# termostat.net
KiCad netlist of a schematic drawn in EAGLE
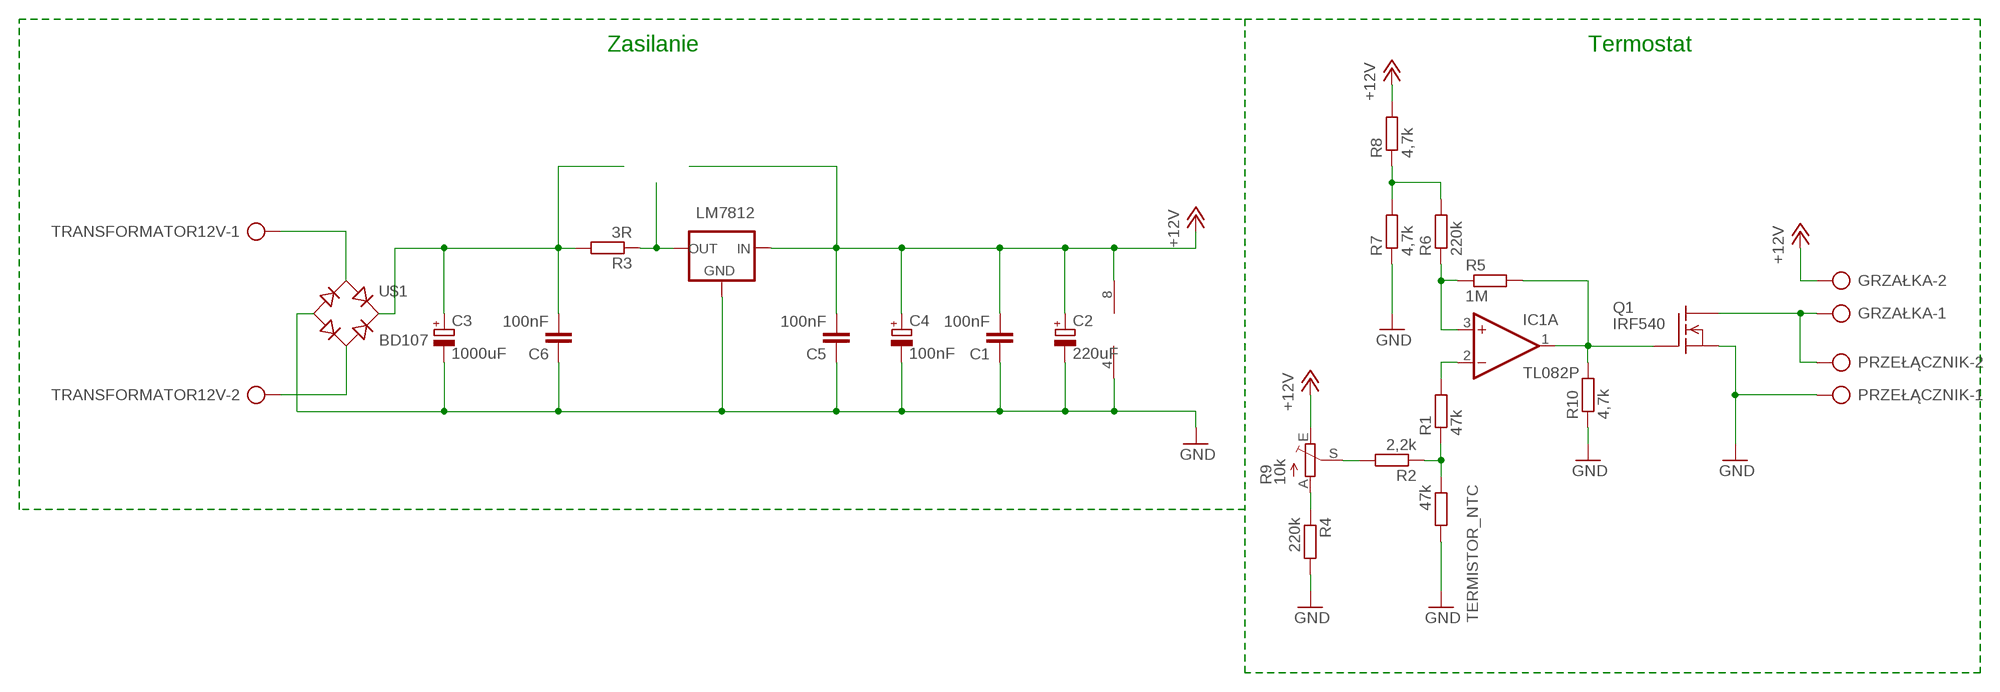
[diagram p0: schematic, sheet 1]

(export (version "E")
  (design (tool "Eeschema 10.0.6"))
  (components
    (comp (ref "C1")
      (value "100nF")
      (footprint "eagle-import:C50-45-75")
      (libsource (lib "eagle-import") (part "C-EU050-045-075"))
    )
    (comp (ref "C2")
      (value "220uF")
      (footprint "eagle-import:E2,5-6")
      (libsource (lib "eagle-import") (part "C-EU-POL'"))
    )
    (comp (ref "C3")
      (value "1000uF")
      (footprint "eagle-import:E5-13")
      (libsource (lib "eagle-import") (part "C-EU-POL"))
    )
    (comp (ref "C4")
      (value "100nF")
      (footprint "eagle-import:E2,5-6")
      (libsource (lib "eagle-import") (part "C-EU-POL'"))
    )
    (comp (ref "C5")
      (value "100nF")
      (footprint "eagle-import:C50-45-75")
      (libsource (lib "eagle-import") (part "C-EU050-045-075"))
    )
    (comp (ref "C6")
      (value "100nF")
      (footprint "eagle-import:C50-45-75")
      (libsource (lib "eagle-import") (part "C-EU050-045-075"))
    )
    (comp (ref "GRZAŁKA")
      (value "AK300/2")
      (footprint "eagle-import:AK300_2")
      (libsource (lib "eagle-import") (part "AK300/2"))
    )
    (comp (ref "IC1")
      (value "TL082P")
      (footprint "eagle-import:DIL08")
      (libsource (lib "eagle-import") (part "TL082P"))
    )
    (comp (ref "LM7812")
      (value "79XXS")
      (footprint "eagle-import:79XXS")
      (libsource (lib "eagle-import") (part "79XXS"))
    )
    (comp (ref "PRZEŁĄCZNIK")
      (value "AK300/2")
      (footprint "eagle-import:AK300_2")
      (libsource (lib "eagle-import") (part "AK300/2"))
    )
    (comp (ref "Q1")
      (value "IRF540")
      (footprint "eagle-import:TO220")
      (libsource (lib "eagle-import") (part "IRF540"))
    )
    (comp (ref "R1")
      (value "47k")
      (footprint "eagle-import:204_7")
      (libsource (lib "eagle-import") (part "R-EU7"))
    )
    (comp (ref "R2")
      (value "2,2k")
      (footprint "eagle-import:204_7")
      (libsource (lib "eagle-import") (part "R-EU7"))
    )
    (comp (ref "R3")
      (value "3R")
      (footprint "eagle-import:204_7")
      (libsource (lib "eagle-import") (part "R-EU7"))
    )
    (comp (ref "R4")
      (value "220k")
      (footprint "eagle-import:204_7")
      (libsource (lib "eagle-import") (part "R-EU7"))
    )
    (comp (ref "R5")
      (value "1M")
      (footprint "eagle-import:204_7")
      (libsource (lib "eagle-import") (part "R-EU7"))
    )
    (comp (ref "R6")
      (value "220k")
      (footprint "eagle-import:204_7")
      (libsource (lib "eagle-import") (part "R-EU7"))
    )
    (comp (ref "R7")
      (value "4,7k")
      (footprint "eagle-import:204_7")
      (libsource (lib "eagle-import") (part "R-EU7"))
    )
    (comp (ref "R8")
      (value "4,7k")
      (footprint "eagle-import:204_7")
      (libsource (lib "eagle-import") (part "R-EU7"))
    )
    (comp (ref "R9")
      (value "10k")
      (footprint "eagle-import:CA6V")
      (libsource (lib "eagle-import") (part "TRIM_EU-CA6V"))
    )
    (comp (ref "R10")
      (value "4,7k")
      (footprint "eagle-import:204_7")
      (libsource (lib "eagle-import") (part "R-EU7"))
    )
    (comp (ref "TERMISTOR_NTC")
      (value "47k")
      (footprint "eagle-import:204_7")
      (libsource (lib "eagle-import") (part "R-EU7"))
    )
    (comp (ref "TRANSFORMATOR12V")
      (value "AK300/2")
      (footprint "eagle-import:AK300_2")
      (libsource (lib "eagle-import") (part "AK300/2"))
    )
    (comp (ref "U$1")
      (value "BD107")
      (footprint "eagle-import:B-DIL")
      (libsource (lib "eagle-import") (part "BD107"))
    )
  )
  (nets
    (net (code "1") (name "+12V") (class "Default")
      (node (ref "C1") (pin "P$2") (pinfunction "2_P$2") (pintype "passive"))
      (node (ref "C2") (pin "P$1") (pinfunction "+_P$1") (pintype "passive"))
      (node (ref "C4") (pin "P$1") (pinfunction "+_P$1") (pintype "passive"))
      (node (ref "C5") (pin "P$2") (pinfunction "2_P$2") (pintype "passive"))
      (node (ref "GRZAŁKA") (pin "2") (pinfunction "KL_2") (pintype "passive"))
      (node (ref "IC1") (pin "8") (pinfunction "V+_8") (pintype "power_in"))
      (node (ref "LM7812") (pin "IN") (pinfunction "IN_IN") (pintype "input"))
      (node (ref "R8") (pin "P$2") (pinfunction "2_P$2") (pintype "passive"))
      (node (ref "R9") (pin "E") (pinfunction "E_E") (pintype "passive"))
    )
    (net (code "2") (name "GND") (class "Default")
      (node (ref "C1") (pin "P$1") (pinfunction "1_P$1") (pintype "passive"))
      (node (ref "C2") (pin "P$2") (pinfunction "-_P$2") (pintype "passive"))
      (node (ref "C3") (pin "P$2") (pinfunction "-_P$2") (pintype "passive"))
      (node (ref "C4") (pin "P$2") (pinfunction "-_P$2") (pintype "passive"))
      (node (ref "C5") (pin "P$1") (pinfunction "1_P$1") (pintype "passive"))
      (node (ref "C6") (pin "P$1") (pinfunction "1_P$1") (pintype "passive"))
      (node (ref "IC1") (pin "4") (pinfunction "V-_4") (pintype "power_in"))
      (node (ref "LM7812") (pin "GND") (pinfunction "GND_GND") (pintype "input"))
      (node (ref "PRZEŁĄCZNIK") (pin "1") (pinfunction "KL_1") (pintype "passive"))
      (node (ref "Q1") (pin "3") (pinfunction "S_3") (pintype "passive"))
      (node (ref "R10") (pin "P$1") (pinfunction "1_P$1") (pintype "passive"))
      (node (ref "R4") (pin "P$2") (pinfunction "2_P$2") (pintype "passive"))
      (node (ref "R7") (pin "P$1") (pinfunction "1_P$1") (pintype "passive"))
      (node (ref "TERMISTOR_NTC") (pin "P$2") (pinfunction "2_P$2") (pintype "passive"))
      (node (ref "U$1") (pin "-") (pinfunction "-_-") (pintype "passive"))
    )
    (net (code "3") (name "Net-(C3-+)") (class "Default")
      (node (ref "C3") (pin "P$1") (pinfunction "+_P$1") (pintype "passive"))
      (node (ref "C6") (pin "P$2") (pinfunction "2_P$2") (pintype "passive"))
      (node (ref "R3") (pin "P$2") (pinfunction "2_P$2") (pintype "passive"))
      (node (ref "U$1") (pin "+") (pinfunction "+_+") (pintype "passive"))
    )
    (net (code "4") (name "Net-(GRZAŁKAA-KL)") (class "Default")
      (node (ref "GRZAŁKA") (pin "1") (pinfunction "KL_1") (pintype "passive"))
      (node (ref "PRZEŁĄCZNIK") (pin "2") (pinfunction "KL_2") (pintype "passive"))
      (node (ref "Q1") (pin "2") (pinfunction "D_2") (pintype "passive"))
    )
    (net (code "5") (name "Net-(IC1A-+IN)") (class "Default")
      (node (ref "IC1") (pin "3") (pinfunction "+IN_3") (pintype "input"))
      (node (ref "R5") (pin "P$1") (pinfunction "1_P$1") (pintype "passive"))
      (node (ref "R6") (pin "P$1") (pinfunction "1_P$1") (pintype "passive"))
    )
    (net (code "6") (name "Net-(IC1A--IN)") (class "Default")
      (node (ref "IC1") (pin "2") (pinfunction "-IN_2") (pintype "input"))
      (node (ref "R1") (pin "P$2") (pinfunction "2_P$2") (pintype "passive"))
    )
    (net (code "7") (name "Net-(IC1A-OUT)") (class "Default")
      (node (ref "IC1") (pin "1") (pinfunction "OUT_1") (pintype "output"))
      (node (ref "Q1") (pin "1") (pinfunction "G_1") (pintype "passive"))
      (node (ref "R10") (pin "P$2") (pinfunction "2_P$2") (pintype "passive"))
      (node (ref "R5") (pin "P$2") (pinfunction "2_P$2") (pintype "passive"))
    )
    (net (code "8") (name "Net-(R1-1)") (class "Default")
      (node (ref "R1") (pin "P$1") (pinfunction "1_P$1") (pintype "passive"))
      (node (ref "R2") (pin "P$1") (pinfunction "1_P$1") (pintype "passive"))
      (node (ref "TERMISTOR_NTC") (pin "P$1") (pinfunction "1_P$1") (pintype "passive"))
    )
    (net (code "9") (name "Net-(R2-2)") (class "Default")
      (node (ref "R2") (pin "P$2") (pinfunction "2_P$2") (pintype "passive"))
      (node (ref "R9") (pin "S") (pinfunction "S_S") (pintype "passive"))
    )
    (net (code "10") (name "Net-(R3-1)") (class "Default")
      (node (ref "LM7812") (pin "OUT") (pinfunction "OUT_OUT") (pintype "passive"))
      (node (ref "R3") (pin "P$1") (pinfunction "1_P$1") (pintype "passive"))
    )
    (net (code "11") (name "Net-(R4-1)") (class "Default")
      (node (ref "R4") (pin "P$1") (pinfunction "1_P$1") (pintype "passive"))
      (node (ref "R9") (pin "A") (pinfunction "A_A") (pintype "passive"))
    )
    (net (code "12") (name "Net-(R6-2)") (class "Default")
      (node (ref "R6") (pin "P$2") (pinfunction "2_P$2") (pintype "passive"))
      (node (ref "R7") (pin "P$2") (pinfunction "2_P$2") (pintype "passive"))
      (node (ref "R8") (pin "P$1") (pinfunction "1_P$1") (pintype "passive"))
    )
    (net (code "13") (name "Net-(TRANSFORMATOR12VA-KL)") (class "Default")
      (node (ref "TRANSFORMATOR12V") (pin "1") (pinfunction "KL_1") (pintype "passive"))
      (node (ref "U$1") (pin "AC1") (pinfunction "AC1_AC1") (pintype "passive"))
    )
    (net (code "14") (name "Net-(TRANSFORMATOR12VB-KL)") (class "Default")
      (node (ref "TRANSFORMATOR12V") (pin "2") (pinfunction "KL_2") (pintype "passive"))
      (node (ref "U$1") (pin "AC2") (pinfunction "AC2_AC2") (pintype "passive"))
    )
  )
)
